# Heater_conn.net
KiCad netlist of a schematic drawn in Altium Designer
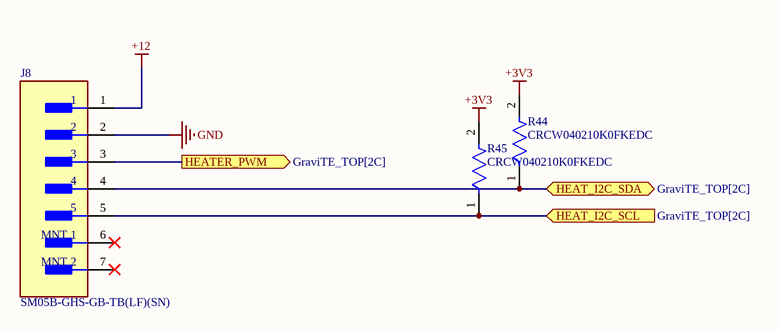
[diagram p0: Heater_conn.SchDoc]

(export (version "E")
  (design (tool "Eeschema 10.0.6"))
  (components
    (comp (ref "J8")
      (value "SM05B-GHS-GB-TB(LF)(SN)")
      (footprint "FP-SM05B-GHS-GB-TB_LF_SN-MFG")
      (description "Connector Header Surface Mount, Right Angle 5 position 0.049\" (1.25mm)")
      (libsource (lib "Altium Content Vault") (part "8ab9848ea90b119fa28a5ddc5abf419"))
    )
    (comp (ref "R44")
      (value "CRCW040210K0FKEDC")
      (footprint "FP-CRCW0402-C-e3-IPC_C")
      (description "RES 10K OHM 1% 1/16W 0402")
      (fields (field (name "TOLERANCE") "1%"))
      (libsource (lib "Altium Content Vault") (part "1029c3af85768c4190bb7ad29bc67b5"))
    )
    (comp (ref "R45")
      (value "CRCW040210K0FKEDC")
      (footprint "FP-CRCW0402-C-e3-IPC_C")
      (description "RES 10K OHM 1% 1/16W 0402")
      (fields (field (name "TOLERANCE") "1%"))
      (libsource (lib "Altium Content Vault") (part "1029c3af85768c4190bb7ad29bc67b5"))
    )
  )
  (nets
    (net (code "1") (name "+3V3") (class "Default")
      (node (ref "R44") (pin "2") (pinfunction "2_2") (pintype "passive"))
      (node (ref "R45") (pin "2") (pinfunction "2_2") (pintype "passive"))
    )
    (net (code "2") (name "+12") (class "Default")
      (node (ref "J8") (pin "1") (pinfunction "1_1") (pintype "passive"))
    )
    (net (code "3") (name "/HEATER_PWM") (class "Default")
      (node (ref "J8") (pin "3") (pinfunction "3_3") (pintype "passive"))
    )
    (net (code "4") (name "/HEAT_I2C_SCL") (class "Default")
      (node (ref "J8") (pin "5") (pinfunction "5_5") (pintype "passive"))
      (node (ref "R45") (pin "1") (pinfunction "1_1") (pintype "passive"))
    )
    (net (code "5") (name "/HEAT_I2C_SDA") (class "Default")
      (node (ref "J8") (pin "4") (pinfunction "4_4") (pintype "passive"))
      (node (ref "R44") (pin "1") (pinfunction "1_1") (pintype "passive"))
    )
    (net (code "6") (name "GND") (class "Default")
      (node (ref "J8") (pin "2") (pinfunction "2_2") (pintype "passive"))
    )
    (net (code "7") (name "unconnected-(J8-MNT_1-Pad6)") (class "Default")
      (node (ref "J8") (pin "6") (pinfunction "MNT_1_6") (pintype "passive+no_connect"))
    )
    (net (code "8") (name "unconnected-(J8-MNT_2-Pad7)") (class "Default")
      (node (ref "J8") (pin "7") (pinfunction "MNT_2_7") (pintype "passive+no_connect"))
    )
  )
)
